# Accelerometer.net
KiCad netlist of a schematic drawn in Altium Designer
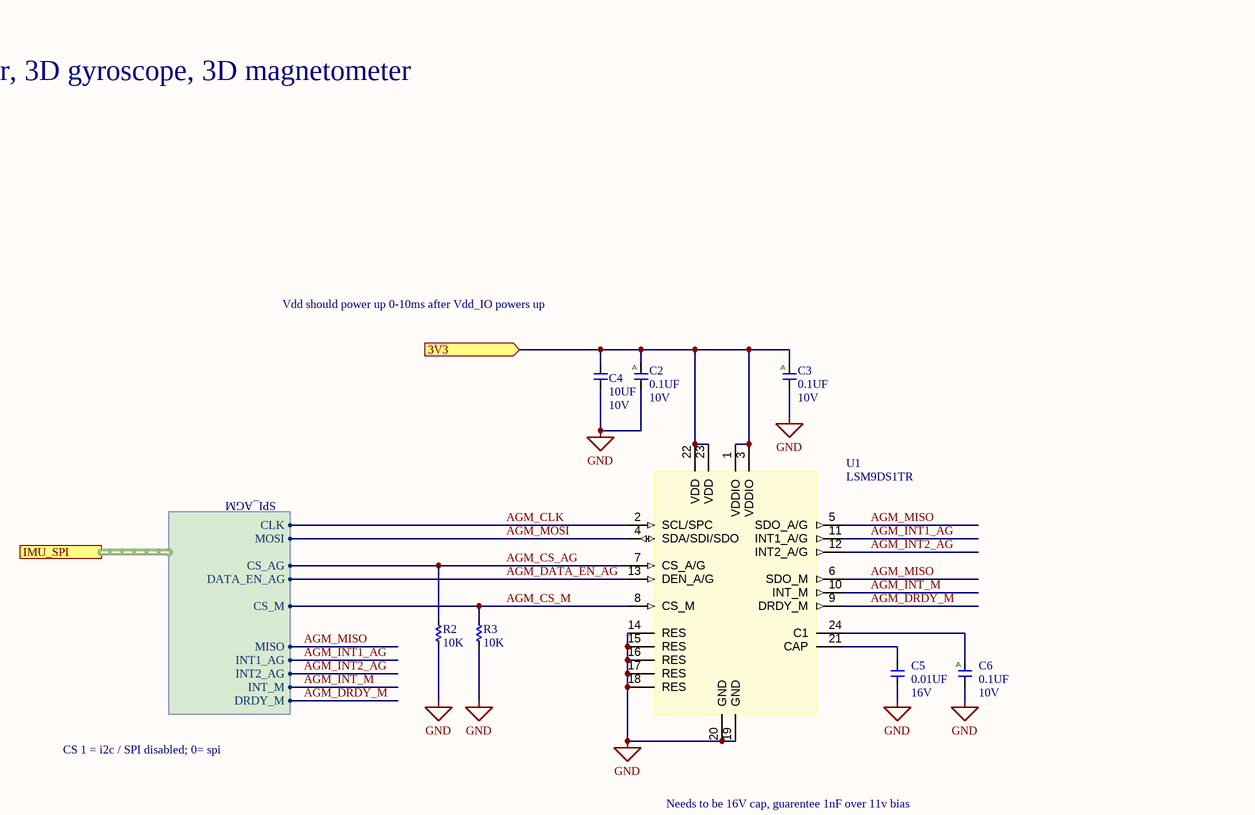
[diagram p0: Accelerometer.SchDoc]

(export (version "E")
  (design (tool "Eeschema 10.0.6"))
  (components
    (comp (ref "C2")
      (value "0.1UF")
      (footprint "C0201Y")
      (description "CAP, CER, X6S, 0.1uF, 10V, 10%, 0201, AUTOGRADE")
      (fields (field (name "MFG") "MURATA") (field (name "VOLTAGE") "10V") (field (name "TOLERANCE") "10%"))
      (libsource (lib "AltiumReleaseLibDB") (part "__Template_Cap_Auto"))
    )
    (comp (ref "C3")
      (value "0.1UF")
      (footprint "C0201Y")
      (description "CAP, CER, X6S, 0.1uF, 10V, 10%, 0201, AUTOGRADE")
      (fields (field (name "MFG") "MURATA") (field (name "VOLTAGE") "10V") (field (name "TOLERANCE") "10%"))
      (libsource (lib "AltiumReleaseLibDB") (part "__Template_Cap_Auto"))
    )
    (comp (ref "C4")
      (value "10UF")
      (footprint "C0402")
      (description "CAP, CER, X5R, 10uF, 10V, 20%, 0402, 0.7mm T")
      (fields (field (name "MFG") "SAMSUNG") (field (name "VOLTAGE") "10V") (field (name "TOLERANCE") "20%"))
      (libsource (lib "AltiumReleaseLibDB") (part "__Template_Cap"))
    )
    (comp (ref "C5")
      (value "0.01UF")
      (footprint "C0201Y")
      (description "CAP, CER, X5R, 0.01uF, 16V, 10%, 0201, 0.33mm T")
      (fields (field (name "MFG") "MURATA") (field (name "VOLTAGE") "16V") (field (name "TOLERANCE") "10%"))
      (libsource (lib "AltiumReleaseLibDB") (part "__Template_Cap"))
    )
    (comp (ref "C6")
      (value "0.1UF")
      (footprint "C0201Y")
      (description "CAP, CER, X6S, 0.1uF, 10V, 10%, 0201, AUTOGRADE")
      (fields (field (name "MFG") "MURATA") (field (name "VOLTAGE") "10V") (field (name "TOLERANCE") "10%"))
      (libsource (lib "AltiumReleaseLibDB") (part "__Template_Cap_Auto"))
    )
    (comp (ref "R2")
      (value "10K")
      (footprint "R0201_H0.26MM")
      (description "RES, 10K, 1%, 1/20W, 0201, AUTOGRADE")
      (fields (field (name "MFG") "PANASONIC") (field (name "POWER") "1/20W"))
      (libsource (lib "AltiumReleaseLibDB") (part "__Template_Resistor"))
    )
    (comp (ref "R3")
      (value "10K")
      (footprint "R0201_H0.26MM")
      (description "RES, 10K, 1%, 1/20W, 0201, AUTOGRADE")
      (fields (field (name "MFG") "PANASONIC") (field (name "POWER") "1/20W"))
      (libsource (lib "AltiumReleaseLibDB") (part "__Template_Resistor"))
    )
    (comp (ref "U1")
      (value "SENSOR_ST_LSM9DS1TR")
      (footprint "LGA24RX8X4_350X100X102")
      (description "SENSOR, MOTION, IMU, ACCELEROMETER/GYROSCOPE/MAGNETOMETER, I2C, SPI, LGA-24")
      (fields (field (name "MFG") "STMicroelectronics") (field (name "MFG P/N") "LSM9DS1TR"))
      (libsource (lib "AltiumReleaseLibDB") (part "SENSOR_ST_LSM9DS1TR"))
    )
  )
  (nets
    (net (code "2") (name "/3V3") (class "Default")
      (node (ref "C2") (pin "1") (pintype "passive"))
      (node (ref "C3") (pin "1") (pintype "passive"))
      (node (ref "C4") (pin "1") (pintype "passive"))
      (node (ref "U1") (pin "1") (pinfunction "VDDIO_1") (pintype "power_in"))
      (node (ref "U1") (pin "22") (pinfunction "VDD_22") (pintype "power_in"))
      (node (ref "U1") (pin "23") (pinfunction "VDD_23") (pintype "power_in"))
      (node (ref "U1") (pin "3") (pinfunction "VDDIO_3") (pintype "power_in"))
    )
    (net (code "3") (name "/AGM_CLK") (class "Default")
      (node (ref "U1") (pin "2") (pinfunction "SCL/SPC_2") (pintype "input"))
    )
    (net (code "4") (name "/AGM_CS_AG") (class "Default")
      (node (ref "R2") (pin "2") (pintype "passive"))
      (node (ref "U1") (pin "7") (pinfunction "CS_A/G_7") (pintype "input"))
    )
    (net (code "5") (name "/AGM_CS_M") (class "Default")
      (node (ref "R3") (pin "2") (pintype "passive"))
      (node (ref "U1") (pin "8") (pinfunction "CS_M_8") (pintype "input"))
    )
    (net (code "6") (name "/AGM_DATA_EN_AG") (class "Default")
      (node (ref "U1") (pin "13") (pinfunction "DEN_A/G_13") (pintype "input"))
    )
    (net (code "7") (name "/AGM_DRDY_M") (class "Default")
      (node (ref "U1") (pin "9") (pinfunction "DRDY_M_9") (pintype "output"))
    )
    (net (code "8") (name "/AGM_INT1_AG") (class "Default")
      (node (ref "U1") (pin "11") (pinfunction "INT1_A/G_11") (pintype "output"))
    )
    (net (code "9") (name "/AGM_INT2_AG") (class "Default")
      (node (ref "U1") (pin "12") (pinfunction "INT2_A/G_12") (pintype "output"))
    )
    (net (code "10") (name "/AGM_INT_M") (class "Default")
      (node (ref "U1") (pin "10") (pinfunction "INT_M_10") (pintype "output"))
    )
    (net (code "11") (name "/AGM_MISO") (class "Default")
      (node (ref "U1") (pin "5") (pinfunction "SDO_A/G_5") (pintype "output"))
      (node (ref "U1") (pin "6") (pinfunction "SDO_M_6") (pintype "output"))
    )
    (net (code "12") (name "/AGM_MOSI") (class "Default")
      (node (ref "U1") (pin "4") (pinfunction "SDA/SDI/SDO_4") (pintype "bidirectional"))
    )
    (net (code "14") (name "GND") (class "Default")
      (node (ref "C2") (pin "2") (pintype "passive"))
      (node (ref "C3") (pin "2") (pintype "passive"))
      (node (ref "C4") (pin "2") (pintype "passive"))
      (node (ref "C5") (pin "2") (pintype "passive"))
      (node (ref "C6") (pin "2") (pintype "passive"))
      (node (ref "R2") (pin "1") (pintype "passive"))
      (node (ref "R3") (pin "1") (pintype "passive"))
      (node (ref "U1") (pin "14") (pinfunction "RES_14") (pintype "power_in"))
      (node (ref "U1") (pin "15") (pinfunction "RES_15") (pintype "power_in"))
      (node (ref "U1") (pin "16") (pinfunction "RES_16") (pintype "power_in"))
      (node (ref "U1") (pin "17") (pinfunction "RES_17") (pintype "power_in"))
      (node (ref "U1") (pin "18") (pinfunction "RES_18") (pintype "power_in"))
      (node (ref "U1") (pin "19") (pinfunction "GND_19") (pintype "power_in"))
      (node (ref "U1") (pin "20") (pinfunction "GND_20") (pintype "power_in"))
    )
    (net (code "15") (name "Net-(U1-C1)") (class "Default")
      (node (ref "C6") (pin "1") (pintype "passive"))
      (node (ref "U1") (pin "24") (pinfunction "C1_24") (pintype "passive"))
    )
    (net (code "16") (name "Net-(U1-CAP)") (class "Default")
      (node (ref "C5") (pin "1") (pintype "passive"))
      (node (ref "U1") (pin "21") (pinfunction "CAP_21") (pintype "passive"))
    )
  )
)
